# RobotSomatic.net
KiCad netlist of a schematic drawn in Altium Designer
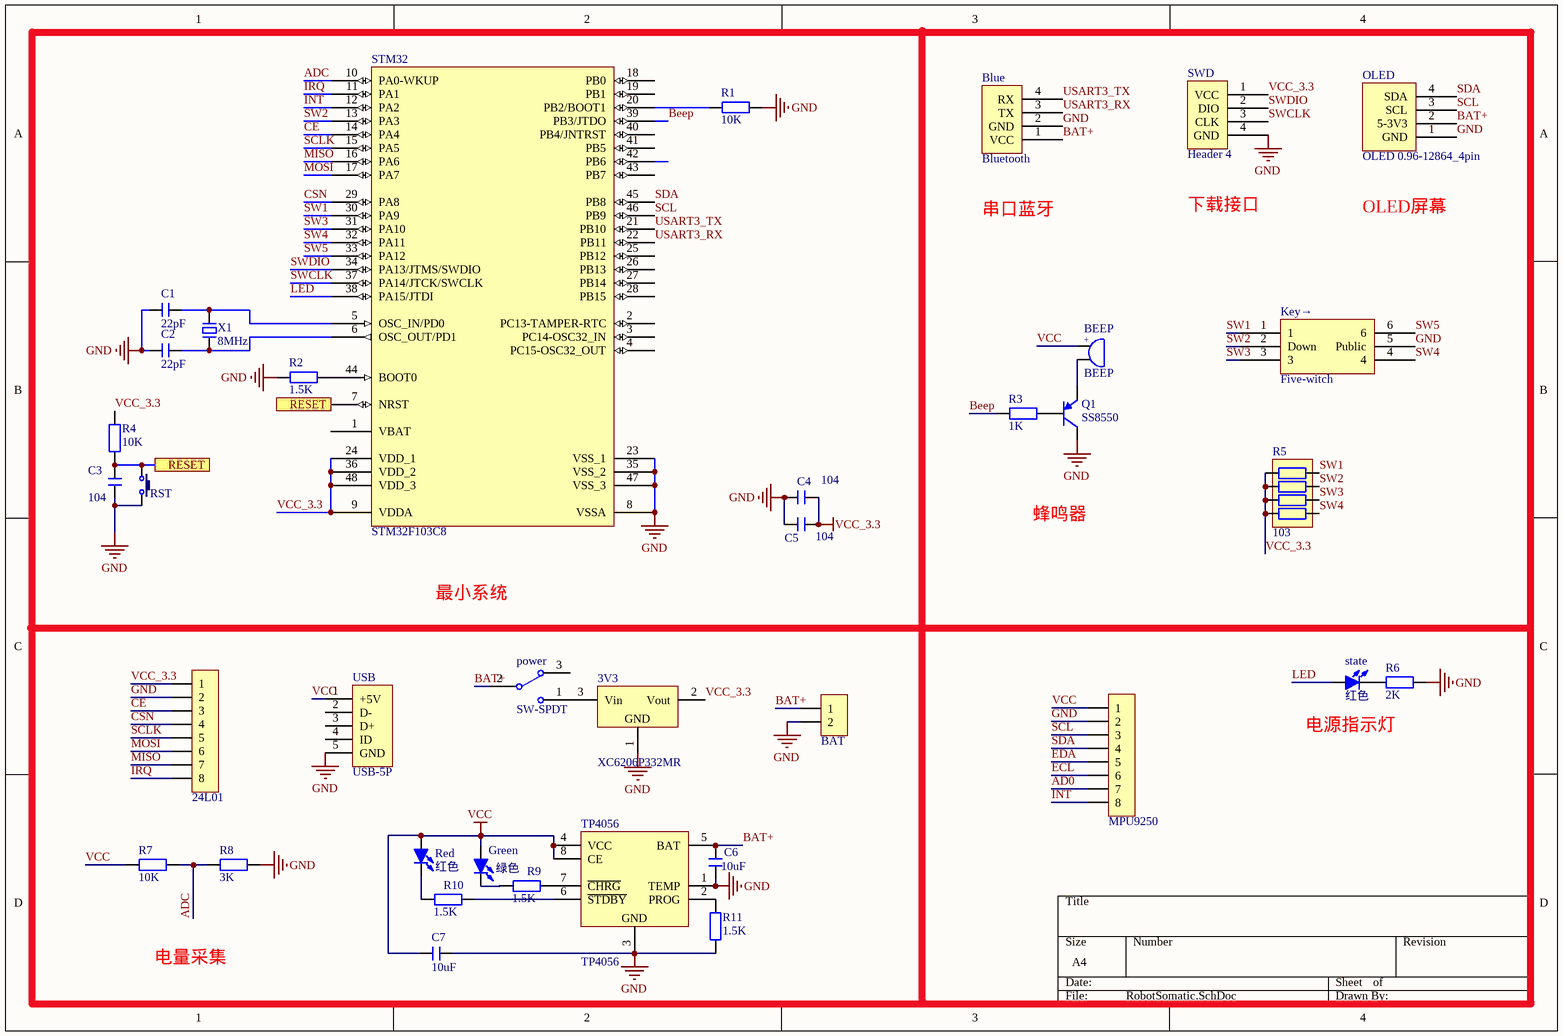
[diagram p0: RobotSomatic.SchDoc]

(export (version "E")
  (design (tool "Eeschema 10.0.6"))
  (components
    (comp (ref "3V3")
      (value "XC6206P332MR")
      (footprint "SOT23-3L")
      (description "3V3三端稳压芯片")
      (fields (field (name "版权归属") "源创客"))
      (libsource (lib "ExpansionBoard") (part "XC6206P332MR"))
    )
    (comp (ref "24L01")
      (value "HDR-1X8")
      (footprint "pad*8")
      (description "8P接插件")
      (fields (field (name "版权归属") "源创客"))
      (libsource (lib "ExpansionBoard") (part "Header 8"))
    )
    (comp (ref "BAT")
      (value "HDR-1X2")
      (footprint "HDR-1X2")
      (description "2P接插件")
      (fields (field (name "版权归属") "源创客"))
      (libsource (lib "ExpansionBoard") (part "Header 2"))
    )
    (comp (ref "BEEP")
      (value "BEEP")
      (footprint "BEEP 5x9x5.5")
      (description "蜂鸣器")
      (fields (field (name "版权归属") "源创客"))
      (libsource (lib "HexapodRobot_STC15F2K60S2") (part "BEEP"))
    )
    (comp (ref "Blue")
      (value "Bluetooth")
      (footprint "HDR-1X4_M")
      (description "蓝牙/串口")
      (libsource (lib "HexapodRobot_STC15F2K60S2") (part "Header4booth"))
    )
    (comp (ref "C1")
      (value "22pF")
      (footprint "C 0603")
      (description "无极性贴片电容")
      (fields (field (name "版权归属") "源创客"))
      (libsource (lib "ExpansionBoard") (part "C"))
    )
    (comp (ref "C2")
      (value "22pF")
      (footprint "C 0603")
      (description "无极性贴片电容")
      (fields (field (name "版权归属") "源创客"))
      (libsource (lib "ExpansionBoard") (part "C"))
    )
    (comp (ref "C3")
      (value "104")
      (footprint "C 0603")
      (description "无极性贴片电容")
      (fields (field (name "版权归属") "源创客"))
      (libsource (lib "ExpansionBoard") (part "C"))
    )
    (comp (ref "C4")
      (value "104")
      (footprint "C 0603")
      (description "无极性贴片电容")
      (fields (field (name "版权归属") "源创客"))
      (libsource (lib "ExpansionBoard") (part "C"))
    )
    (comp (ref "C5")
      (value "104")
      (footprint "C 0603")
      (description "无极性贴片电容")
      (fields (field (name "版权归属") "源创客"))
      (libsource (lib "ExpansionBoard") (part "C"))
    )
    (comp (ref "C6")
      (value "10uF")
      (footprint "C 0603")
      (description "无极性贴片电容")
      (fields (field (name "版权归属") "源创客"))
      (libsource (lib "ExpansionBoard") (part "C"))
    )
    (comp (ref "C7")
      (value "10uF")
      (footprint "C 0603")
      (description "无极性贴片电容")
      (fields (field (name "版权归属") "源创客"))
      (libsource (lib "ExpansionBoard") (part "C"))
    )
    (comp (ref "Green")
      (value "绿色")
      (footprint "LED 0603G")
      (description "贴片LED")
      (fields (field (name "版权归属") "源创客"))
      (libsource (lib "ExpansionBoard") (part "LED-SMD"))
    )
    (comp (ref "Key→")
      (value "Five-witch")
      (footprint "Five-witch")
      (description "五向开关")
      (libsource (lib "ExpansionBoard") (part "Five-witch"))
    )
    (comp (ref "MPU9250")
      (value "HDR-1X8")
      (footprint "HDR2.54-M-LI-8P")
      (description "8P接插件")
      (fields (field (name "版权归属") "源创客"))
      (libsource (lib "ExpansionBoard") (part "Header 8"))
    )
    (comp (ref "OLED")
      (value "OLED 0.96-12864_4pin")
      (footprint "OLED 0.96-12864_4pin")
      (description "12864 点阵屏")
      (libsource (lib "HexapodRobot_STC15W4K48S4") (part "OLED 0.96-12864_4pin"))
    )
    (comp (ref "power")
      (value "SW-SPDT")
      (footprint "KEY_HDR3")
      (description "开关")
      (fields (field (name "PUBLISHER") "Altium Limited"))
      (libsource (lib "ExpansionBoard") (part "SW-SPDT"))
    )
    (comp (ref "Q1")
      (value "SS8550")
      (footprint "TO92A")
      (description "高频放大-PNP型")
      (fields (field (name "版权归属") "源创客"))
      (libsource (lib "HexapodRobot_STC15F2K60S2") (part "8550-DIP"))
    )
    (comp (ref "R1")
      (value "10K")
      (footprint "R 0603")
      (description "贴片电阻")
      (fields (field (name "版权归属") "源创客"))
      (libsource (lib "ExpansionBoard") (part "R"))
    )
    (comp (ref "R2")
      (value "1.5K")
      (footprint "R 0603")
      (description "贴片电阻")
      (fields (field (name "版权归属") "源创客"))
      (libsource (lib "ExpansionBoard") (part "R"))
    )
    (comp (ref "R3")
      (value "1K")
      (footprint "R 0603")
      (description "贴片电阻")
      (fields (field (name "版权归属") "源创客"))
      (libsource (lib "HexapodRobot_STC15F2K60S2") (part "R"))
    )
    (comp (ref "R4")
      (value "10K")
      (footprint "R 0603")
      (description "贴片电阻")
      (fields (field (name "版权归属") "源创客"))
      (libsource (lib "ExpansionBoard") (part "R"))
    )
    (comp (ref "R5")
      (value "103")
      (footprint "RCA-8P4R-0603")
      (description "贴片网络排阻")
      (fields (field (name "版权归属") "源创客"))
      (libsource (lib "ExpansionBoard") (part "R-8P4R"))
    )
    (comp (ref "R6")
      (value "2K")
      (footprint "R 0603")
      (description "贴片电阻")
      (fields (field (name "版权归属") "源创客"))
      (libsource (lib "HexapodRobot_STC15F2K60S2") (part "R"))
    )
    (comp (ref "R7")
      (value "10K")
      (footprint "R 0603")
      (description "贴片电阻")
      (fields (field (name "版权归属") "源创客"))
      (libsource (lib "HexapodRobot_STC15F2K60S2") (part "R"))
    )
    (comp (ref "R8")
      (value "3K")
      (footprint "R 0603")
      (description "贴片电阻")
      (fields (field (name "版权归属") "源创客"))
      (libsource (lib "HexapodRobot_STC15F2K60S2") (part "R"))
    )
    (comp (ref "R9")
      (value "1.5K")
      (footprint "R 0603")
      (description "贴片电阻")
      (fields (field (name "版权归属") "源创客"))
      (libsource (lib "ExpansionBoard") (part "R"))
    )
    (comp (ref "R10")
      (value "1.5K")
      (footprint "R 0603")
      (description "贴片电阻")
      (fields (field (name "版权归属") "源创客"))
      (libsource (lib "ExpansionBoard") (part "R"))
    )
    (comp (ref "R11")
      (value "1.5K")
      (footprint "R 0603")
      (description "贴片电阻")
      (fields (field (name "版权归属") "源创客"))
      (libsource (lib "ExpansionBoard") (part "R"))
    )
    (comp (ref "Red")
      (value "红色")
      (footprint "LED 0603R")
      (description "贴片LED")
      (fields (field (name "版权归属") "源创客"))
      (libsource (lib "ExpansionBoard") (part "LED-SMD"))
    )
    (comp (ref "RST")
      (value "3x6x5")
      (footprint "TSW SMD-3*6*2.5")
      (description "3x6轻触开关")
      (fields (field (name "版权归属") "源创客"))
      (libsource (lib "ExpansionBoard") (part "TSW 3x6"))
    )
    (comp (ref "state")
      (value "红色")
      (footprint "LED 0603R")
      (description "贴片LED")
      (fields (field (name "版权归属") "源创客"))
      (libsource (lib "HexapodRobot_STC15F2K60S2") (part "LED-SMD"))
    )
    (comp (ref "STM32")
      (value "STM32F103C8")
      (footprint "LQFP48 7X7_N")
      (description "Flaah:64/RAM:20/IO:36")
      (fields (field (name "版权归属") "源创客"))
      (libsource (lib "ExpansionBoard") (part "STM32F103C8"))
    )
    (comp (ref "SWD")
      (value "Header 4")
      (footprint "HDR-1X4")
      (description "SWD")
      (fields (field (name "PUBLISHER") "Altium Limited"))
      (libsource (lib "ExpansionBoard") (part "Header 4"))
    )
    (comp (ref "TP4056")
      (value "TP4056")
      (footprint "SOP8_N")
      (description "锂电池充电管理")
      (fields (field (name "版权归属") "源创客"))
      (libsource (lib "ExpansionBoard") (part "TP4056"))
    )
    (comp (ref "USB")
      (value "USB-5P")
      (footprint "USB-MICRO_A")
      (description "微型USB母座")
      (fields (field (name "版权归属") "源创客"))
      (libsource (lib "ExpansionBoard") (part "USB-5P"))
    )
    (comp (ref "X1")
      (value "8MHz")
      (footprint "XTAL-49S DIP")
      (description "2脚晶振")
      (fields (field (name "版权归属") "源创客"))
      (libsource (lib "ExpansionBoard") (part "XTAL-2"))
    )
  )
  (nets
    (net (code "1") (name "/AD0") (class "Default")
      (node (ref "MPU9250") (pin "7") (pinfunction "7_7") (pintype "passive"))
    )
    (net (code "2") (name "/ADC") (class "Default")
      (node (ref "R7") (pin "2") (pinfunction "2_2") (pintype "passive"))
      (node (ref "R8") (pin "1") (pinfunction "1_1") (pintype "passive"))
      (node (ref "STM32") (pin "10") (pinfunction "PA0-WKUP_10") (pintype "bidirectional"))
    )
    (net (code "3") (name "/BAT+") (class "Default")
      (node (ref "BAT") (pin "1") (pinfunction "1_1") (pintype "passive"))
      (node (ref "Blue") (pin "1") (pinfunction "VCC_1") (pintype "passive"))
      (node (ref "C6") (pin "2") (pinfunction "2_2") (pintype "passive"))
      (node (ref "OLED") (pin "2") (pinfunction "5-3V3_2") (pintype "passive"))
      (node (ref "TP4056") (pin "5") (pinfunction "BAT_5") (pintype "passive"))
      (node (ref "power") (pin "2") (pinfunction "2_2") (pintype "passive"))
    )
    (net (code "4") (name "/Beep") (class "Default")
      (node (ref "R3") (pin "1") (pinfunction "1_1") (pintype "passive"))
      (node (ref "STM32") (pin "39") (pinfunction "PB3/JTDO_39") (pintype "bidirectional"))
    )
    (net (code "5") (name "/CE") (class "Default")
      (node (ref "24L01") (pin "3") (pinfunction "3_3") (pintype "passive"))
      (node (ref "STM32") (pin "14") (pinfunction "PA4_14") (pintype "bidirectional"))
    )
    (net (code "6") (name "/CSN") (class "Default")
      (node (ref "24L01") (pin "4") (pinfunction "4_4") (pintype "passive"))
      (node (ref "STM32") (pin "29") (pinfunction "PA8_29") (pintype "bidirectional"))
    )
    (net (code "7") (name "/ECL") (class "Default")
      (node (ref "MPU9250") (pin "6") (pinfunction "6_6") (pintype "passive"))
    )
    (net (code "8") (name "/EDA") (class "Default")
      (node (ref "MPU9250") (pin "5") (pinfunction "5_5") (pintype "passive"))
    )
    (net (code "9") (name "/INT") (class "Default")
      (node (ref "MPU9250") (pin "8") (pinfunction "8_8") (pintype "passive"))
      (node (ref "STM32") (pin "12") (pinfunction "PA2_12") (pintype "bidirectional"))
    )
    (net (code "10") (name "/IRQ") (class "Default")
      (node (ref "24L01") (pin "8") (pinfunction "8_8") (pintype "passive"))
      (node (ref "STM32") (pin "11") (pinfunction "PA1_11") (pintype "bidirectional"))
    )
    (net (code "11") (name "/LED") (class "Default")
      (node (ref "STM32") (pin "38") (pinfunction "PA15/JTDI_38") (pintype "bidirectional"))
      (node (ref "state") (pin "1") (pinfunction "A_1") (pintype "passive"))
    )
    (net (code "12") (name "/MISO") (class "Default")
      (node (ref "24L01") (pin "7") (pinfunction "7_7") (pintype "passive"))
      (node (ref "STM32") (pin "16") (pinfunction "PA6_16") (pintype "bidirectional"))
    )
    (net (code "13") (name "/MOSI") (class "Default")
      (node (ref "24L01") (pin "6") (pinfunction "6_6") (pintype "passive"))
      (node (ref "STM32") (pin "17") (pinfunction "PA7_17") (pintype "bidirectional"))
    )
    (net (code "14") (name "/RESET") (class "Default")
      (node (ref "C3") (pin "2") (pinfunction "2_2") (pintype "passive"))
      (node (ref "R4") (pin "1") (pinfunction "1_1") (pintype "passive"))
      (node (ref "RST") (pin "1") (pinfunction "1_1") (pintype "passive"))
      (node (ref "STM32") (pin "7") (pinfunction "NRST_7") (pintype "bidirectional"))
    )
    (net (code "15") (name "/SCL") (class "Default")
      (node (ref "MPU9250") (pin "3") (pinfunction "3_3") (pintype "passive"))
      (node (ref "OLED") (pin "3") (pinfunction "SCL_3") (pintype "passive"))
      (node (ref "STM32") (pin "46") (pinfunction "PB9_46") (pintype "bidirectional"))
    )
    (net (code "16") (name "/SCLK") (class "Default")
      (node (ref "24L01") (pin "5") (pinfunction "5_5") (pintype "passive"))
      (node (ref "STM32") (pin "15") (pinfunction "PA5_15") (pintype "bidirectional"))
    )
    (net (code "17") (name "/SDA") (class "Default")
      (node (ref "MPU9250") (pin "4") (pinfunction "4_4") (pintype "passive"))
      (node (ref "OLED") (pin "4") (pinfunction "SDA_4") (pintype "passive"))
      (node (ref "STM32") (pin "45") (pinfunction "PB8_45") (pintype "bidirectional"))
    )
    (net (code "18") (name "/SW1") (class "Default")
      (node (ref "Key→") (pin "1") (pinfunction "1_1") (pintype "passive"))
      (node (ref "R5") (pin "8") (pinfunction "8_8") (pintype "passive"))
      (node (ref "STM32") (pin "30") (pinfunction "PA9_30") (pintype "bidirectional"))
    )
    (net (code "19") (name "/SW2") (class "Default")
      (node (ref "Key→") (pin "2") (pinfunction "Down_2") (pintype "passive"))
      (node (ref "R5") (pin "7") (pinfunction "7_7") (pintype "passive"))
      (node (ref "STM32") (pin "13") (pinfunction "PA3_13") (pintype "bidirectional"))
    )
    (net (code "20") (name "/SW3") (class "Default")
      (node (ref "Key→") (pin "3") (pinfunction "3_3") (pintype "passive"))
      (node (ref "R5") (pin "6") (pinfunction "6_6") (pintype "passive"))
      (node (ref "STM32") (pin "31") (pinfunction "PA10_31") (pintype "bidirectional"))
    )
    (net (code "21") (name "/SW4") (class "Default")
      (node (ref "Key→") (pin "4") (pinfunction "4_4") (pintype "passive"))
      (node (ref "R5") (pin "5") (pinfunction "5_5") (pintype "passive"))
      (node (ref "STM32") (pin "32") (pinfunction "PA11_32") (pintype "bidirectional"))
    )
    (net (code "22") (name "/SW5") (class "Default")
      (node (ref "Key→") (pin "6") (pinfunction "6_6") (pintype "passive"))
      (node (ref "STM32") (pin "33") (pinfunction "PA12_33") (pintype "bidirectional"))
    )
    (net (code "23") (name "/SWCLK") (class "Default")
      (node (ref "STM32") (pin "37") (pinfunction "PA14/JTCK/SWCLK_37") (pintype "bidirectional"))
      (node (ref "SWD") (pin "3") (pinfunction "CLK_3") (pintype "passive"))
    )
    (net (code "24") (name "/SWDIO") (class "Default")
      (node (ref "STM32") (pin "34") (pinfunction "PA13/JTMS/SWDIO_34") (pintype "bidirectional"))
      (node (ref "SWD") (pin "2") (pinfunction "DIO_2") (pintype "passive"))
    )
    (net (code "25") (name "/USART3_RX") (class "Default")
      (node (ref "Blue") (pin "3") (pinfunction "TX_3") (pintype "passive"))
      (node (ref "STM32") (pin "22") (pinfunction "PB11_22") (pintype "bidirectional"))
    )
    (net (code "26") (name "/USART3_TX") (class "Default")
      (node (ref "Blue") (pin "4") (pinfunction "RX_4") (pintype "passive"))
      (node (ref "STM32") (pin "21") (pinfunction "PB10_21") (pintype "bidirectional"))
    )
    (net (code "27") (name "GND") (class "Default")
      (node (ref "24L01") (pin "2") (pinfunction "2_2") (pintype "passive"))
      (node (ref "3V3") (pin "1") (pinfunction "GND_1") (pintype "passive"))
      (node (ref "BAT") (pin "2") (pinfunction "2_2") (pintype "passive"))
      (node (ref "Blue") (pin "2") (pinfunction "GND_2") (pintype "passive"))
      (node (ref "C1") (pin "2") (pinfunction "2_2") (pintype "passive"))
      (node (ref "C2") (pin "2") (pinfunction "2_2") (pintype "passive"))
      (node (ref "C3") (pin "1") (pinfunction "1_1") (pintype "passive"))
      (node (ref "C4") (pin "1") (pinfunction "1_1") (pintype "passive"))
      (node (ref "C5") (pin "1") (pinfunction "1_1") (pintype "passive"))
      (node (ref "C6") (pin "1") (pinfunction "1_1") (pintype "passive"))
      (node (ref "C7") (pin "2") (pinfunction "2_2") (pintype "passive"))
      (node (ref "Key→") (pin "5") (pinfunction "Public_5") (pintype "passive"))
      (node (ref "MPU9250") (pin "2") (pinfunction "2_2") (pintype "passive"))
      (node (ref "OLED") (pin "1") (pinfunction "GND_1") (pintype "passive"))
      (node (ref "Q1") (pin "3") (pinfunction "C_3") (pintype "passive"))
      (node (ref "R1") (pin "2") (pinfunction "2_2") (pintype "passive"))
      (node (ref "R11") (pin "1") (pinfunction "1_1") (pintype "passive"))
      (node (ref "R2") (pin "1") (pinfunction "1_1") (pintype "passive"))
      (node (ref "R6") (pin "2") (pinfunction "2_2") (pintype "passive"))
      (node (ref "R8") (pin "2") (pinfunction "2_2") (pintype "passive"))
      (node (ref "RST") (pin "2") (pinfunction "2_2") (pintype "passive"))
      (node (ref "STM32") (pin "23") (pinfunction "VSS_1_23") (pintype "power_in"))
      (node (ref "STM32") (pin "35") (pinfunction "VSS_2_35") (pintype "power_in"))
      (node (ref "STM32") (pin "47") (pinfunction "VSS_3_47") (pintype "power_in"))
      (node (ref "STM32") (pin "8") (pinfunction "VSSA_8") (pintype "power_in"))
      (node (ref "SWD") (pin "4") (pinfunction "GND_4") (pintype "passive"))
      (node (ref "TP4056") (pin "1") (pinfunction "TEMP_1") (pintype "passive"))
      (node (ref "TP4056") (pin "3") (pinfunction "GND_3") (pintype "passive"))
      (node (ref "USB") (pin "5") (pinfunction "GND_5") (pintype "passive"))
    )
    (net (code "28") (name "Net-(3V3-Vin)") (class "Default")
      (node (ref "3V3") (pin "3") (pinfunction "Vin_3") (pintype "passive"))
      (node (ref "power") (pin "1") (pinfunction "1_1") (pintype "passive"))
    )
    (net (code "29") (name "Net-(Green-K)") (class "Default")
      (node (ref "Green") (pin "2") (pinfunction "K_2") (pintype "passive"))
      (node (ref "R9") (pin "2") (pinfunction "2_2") (pintype "passive"))
    )
    (net (code "30") (name "Net-(Q1-B)") (class "Default")
      (node (ref "Q1") (pin "2") (pinfunction "B_2") (pintype "passive"))
      (node (ref "R3") (pin "2") (pinfunction "2_2") (pintype "passive"))
    )
    (net (code "31") (name "Net-(Q1-E)") (class "Default")
      (node (ref "BEEP") (pin "2") (pinfunction "2_2") (pintype "passive"))
      (node (ref "Q1") (pin "1") (pinfunction "E_1") (pintype "passive"))
    )
    (net (code "32") (name "Net-(Red-K)") (class "Default")
      (node (ref "R10") (pin "1") (pinfunction "1_1") (pintype "passive"))
      (node (ref "Red") (pin "2") (pinfunction "K_2") (pintype "passive"))
    )
    (net (code "33") (name "Net-(STM32-BOOT0)") (class "Default")
      (node (ref "R2") (pin "2") (pinfunction "2_2") (pintype "passive"))
      (node (ref "STM32") (pin "44") (pinfunction "BOOT0_44") (pintype "input"))
    )
    (net (code "34") (name "Net-(STM32-OSC_IN{slash}PD0)") (class "Default")
      (node (ref "C1") (pin "1") (pinfunction "1_1") (pintype "passive"))
      (node (ref "STM32") (pin "5") (pinfunction "OSC_IN/PD0_5") (pintype "input"))
      (node (ref "X1") (pin "2") (pinfunction "2_2") (pintype "passive"))
    )
    (net (code "35") (name "Net-(STM32-OSC_OUT{slash}PD1)") (class "Default")
      (node (ref "C2") (pin "1") (pinfunction "1_1") (pintype "passive"))
      (node (ref "STM32") (pin "6") (pinfunction "OSC_OUT/PD1_6") (pintype "output"))
      (node (ref "X1") (pin "1") (pinfunction "1_1") (pintype "passive"))
    )
    (net (code "36") (name "Net-(STM32-PB2{slash}BOOT1)") (class "Default")
      (node (ref "R1") (pin "1") (pinfunction "1_1") (pintype "passive"))
      (node (ref "STM32") (pin "20") (pinfunction "PB2/BOOT1_20") (pintype "bidirectional"))
    )
    (net (code "37") (name "Net-(TP4056-PROG)") (class "Default")
      (node (ref "R11") (pin "2") (pinfunction "2_2") (pintype "passive"))
      (node (ref "TP4056") (pin "2") (pinfunction "PROG_2") (pintype "passive"))
    )
    (net (code "38") (name "Net-(TP4056-~{CHRG})") (class "Default")
      (node (ref "R9") (pin "1") (pinfunction "1_1") (pintype "passive"))
      (node (ref "TP4056") (pin "7") (pinfunction "~{CHRG}_7") (pintype "passive"))
    )
    (net (code "39") (name "Net-(TP4056-~{STDBY})") (class "Default")
      (node (ref "R10") (pin "2") (pinfunction "2_2") (pintype "passive"))
      (node (ref "TP4056") (pin "6") (pinfunction "~{STDBY}_6") (pintype "passive"))
    )
    (net (code "40") (name "Net-(state-K)") (class "Default")
      (node (ref "R6") (pin "1") (pinfunction "1_1") (pintype "passive"))
      (node (ref "state") (pin "2") (pinfunction "K_2") (pintype "passive"))
    )
    (net (code "41") (name "VCC") (class "Default")
      (node (ref "BEEP") (pin "1") (pinfunction "1_1") (pintype "passive"))
      (node (ref "C7") (pin "1") (pinfunction "1_1") (pintype "passive"))
      (node (ref "Green") (pin "1") (pinfunction "A_1") (pintype "passive"))
      (node (ref "MPU9250") (pin "1") (pinfunction "1_1") (pintype "passive"))
      (node (ref "R7") (pin "1") (pinfunction "1_1") (pintype "passive"))
      (node (ref "Red") (pin "1") (pinfunction "A_1") (pintype "passive"))
      (node (ref "TP4056") (pin "4") (pinfunction "VCC_4") (pintype "passive"))
      (node (ref "TP4056") (pin "8") (pinfunction "CE_8") (pintype "passive"))
      (node (ref "USB") (pin "1") (pinfunction "+5V_1") (pintype "passive"))
    )
    (net (code "42") (name "VCC_3.3") (class "Default")
      (node (ref "24L01") (pin "1") (pinfunction "1_1") (pintype "passive"))
      (node (ref "3V3") (pin "2") (pinfunction "Vout_2") (pintype "passive"))
      (node (ref "C4") (pin "2") (pinfunction "2_2") (pintype "passive"))
      (node (ref "C5") (pin "2") (pinfunction "2_2") (pintype "passive"))
      (node (ref "R4") (pin "2") (pinfunction "2_2") (pintype "passive"))
      (node (ref "R5") (pin "1") (pinfunction "1_1") (pintype "passive"))
      (node (ref "R5") (pin "2") (pinfunction "2_2") (pintype "passive"))
      (node (ref "R5") (pin "3") (pinfunction "3_3") (pintype "passive"))
      (node (ref "R5") (pin "4") (pinfunction "4_4") (pintype "passive"))
      (node (ref "STM32") (pin "24") (pinfunction "VDD_1_24") (pintype "power_in"))
      (node (ref "STM32") (pin "36") (pinfunction "VDD_2_36") (pintype "power_in"))
      (node (ref "STM32") (pin "48") (pinfunction "VDD_3_48") (pintype "power_in"))
      (node (ref "STM32") (pin "9") (pinfunction "VDDA_9") (pintype "power_in"))
      (node (ref "SWD") (pin "1") (pinfunction "VCC_1") (pintype "passive"))
    )
    (net (code "43") (name "unconnected-(STM32-PB0-Pad18)") (class "Default")
      (node (ref "STM32") (pin "18") (pinfunction "PB0_18") (pintype "bidirectional"))
    )
    (net (code "44") (name "unconnected-(STM32-PB1-Pad19)") (class "Default")
      (node (ref "STM32") (pin "19") (pinfunction "PB1_19") (pintype "bidirectional"))
    )
    (net (code "45") (name "unconnected-(STM32-PB4{slash}JNTRST-Pad40)") (class "Default")
      (node (ref "STM32") (pin "40") (pinfunction "PB4/JNTRST_40") (pintype "bidirectional"))
    )
    (net (code "46") (name "unconnected-(STM32-PB5-Pad41)") (class "Default")
      (node (ref "STM32") (pin "41") (pinfunction "PB5_41") (pintype "bidirectional"))
    )
    (net (code "47") (name "unconnected-(STM32-PB6-Pad42)") (class "Default")
      (node (ref "STM32") (pin "42") (pinfunction "PB6_42") (pintype "bidirectional"))
    )
    (net (code "48") (name "unconnected-(STM32-PB7-Pad43)") (class "Default")
      (node (ref "STM32") (pin "43") (pinfunction "PB7_43") (pintype "bidirectional"))
    )
    (net (code "49") (name "unconnected-(STM32-PB12-Pad25)") (class "Default")
      (node (ref "STM32") (pin "25") (pinfunction "PB12_25") (pintype "bidirectional"))
    )
    (net (code "50") (name "unconnected-(STM32-PB13-Pad26)") (class "Default")
      (node (ref "STM32") (pin "26") (pinfunction "PB13_26") (pintype "bidirectional"))
    )
    (net (code "51") (name "unconnected-(STM32-PB14-Pad27)") (class "Default")
      (node (ref "STM32") (pin "27") (pinfunction "PB14_27") (pintype "bidirectional"))
    )
    (net (code "52") (name "unconnected-(STM32-PB15-Pad28)") (class "Default")
      (node (ref "STM32") (pin "28") (pinfunction "PB15_28") (pintype "bidirectional"))
    )
    (net (code "53") (name "unconnected-(STM32-PC13-TAMPER-RTC-Pad2)") (class "Default")
      (node (ref "STM32") (pin "2") (pinfunction "PC13-TAMPER-RTC_2") (pintype "bidirectional"))
    )
    (net (code "54") (name "unconnected-(STM32-PC14-OSC32_IN-Pad3)") (class "Default")
      (node (ref "STM32") (pin "3") (pinfunction "PC14-OSC32_IN_3") (pintype "bidirectional"))
    )
    (net (code "55") (name "unconnected-(STM32-PC15-OSC32_OUT-Pad4)") (class "Default")
      (node (ref "STM32") (pin "4") (pinfunction "PC15-OSC32_OUT_4") (pintype "bidirectional"))
    )
    (net (code "56") (name "unconnected-(STM32-VBAT-Pad1)") (class "Default")
      (node (ref "STM32") (pin "1") (pinfunction "VBAT_1") (pintype "power_in"))
    )
    (net (code "57") (name "unconnected-(USB-D+-Pad3)") (class "Default")
      (node (ref "USB") (pin "3") (pinfunction "D+_3") (pintype "passive"))
    )
    (net (code "58") (name "unconnected-(USB-D--Pad2)") (class "Default")
      (node (ref "USB") (pin "2") (pinfunction "D-_2") (pintype "passive"))
    )
    (net (code "59") (name "unconnected-(USB-ID-Pad4)") (class "Default")
      (node (ref "USB") (pin "4") (pinfunction "ID_4") (pintype "passive"))
    )
    (net (code "60") (name "unconnected-(power-Pad3)") (class "Default")
      (node (ref "power") (pin "3") (pinfunction "3_3") (pintype "passive"))
    )
  )
)
